# hf-controller.net
KiCad netlist of a schematic drawn in EAGLE
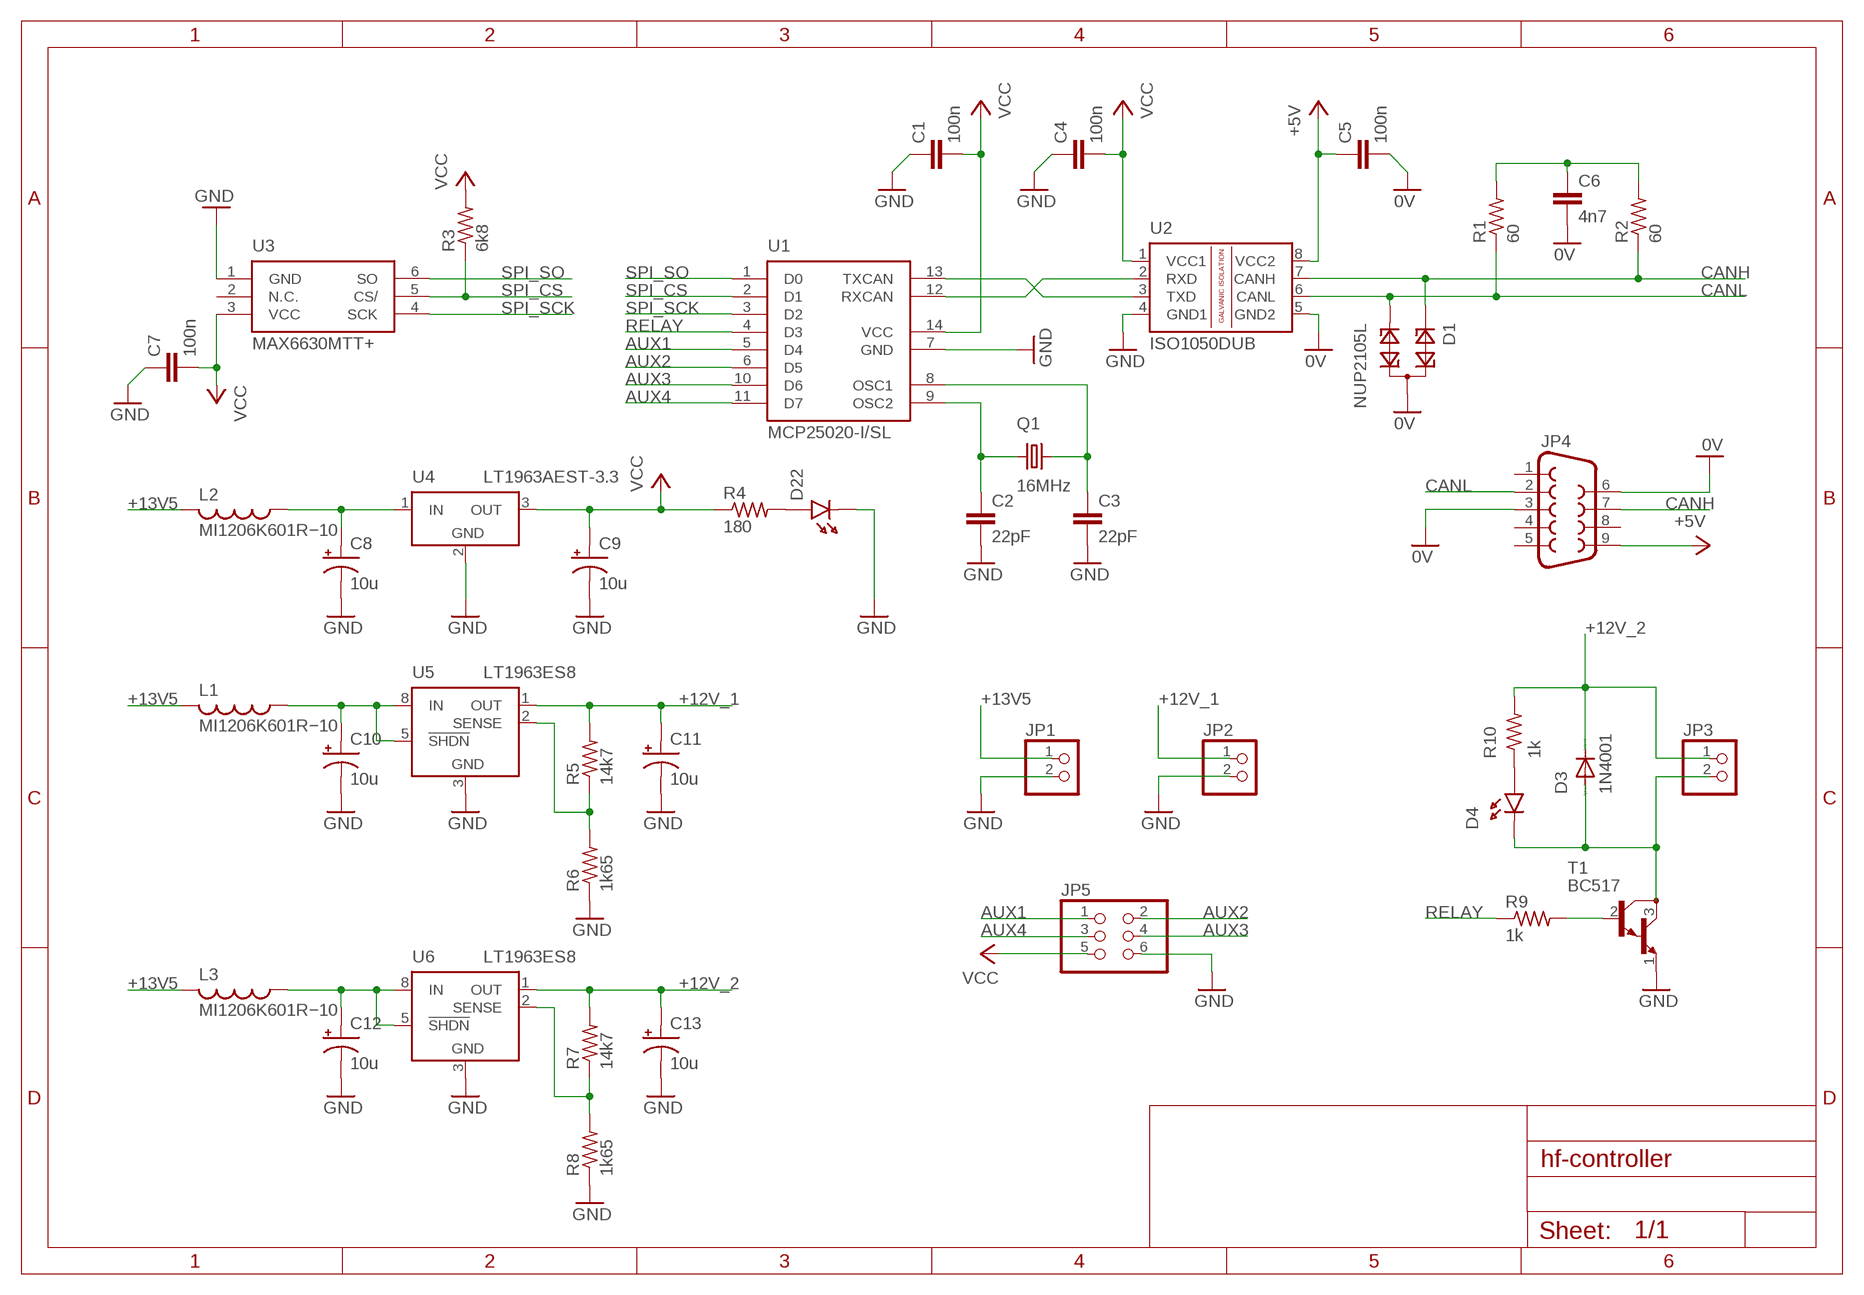
[diagram p0: schematic, sheet 1]

(export (version "E")
  (design (tool "Eeschema 10.0.6"))
  (components
    (comp (ref "C1")
      (value "100n")
      (footprint "eagle-import:C0805")
      (libsource (lib "eagle-import") (part "C-EUC0805"))
    )
    (comp (ref "C2")
      (value "22pF")
      (footprint "eagle-import:C0805")
      (libsource (lib "eagle-import") (part "C-EUC0805"))
    )
    (comp (ref "C3")
      (value "22pF")
      (footprint "eagle-import:C0805")
      (libsource (lib "eagle-import") (part "C-EUC0805"))
    )
    (comp (ref "C4")
      (value "100n")
      (footprint "eagle-import:C0805")
      (libsource (lib "eagle-import") (part "C-EUC0805"))
    )
    (comp (ref "C5")
      (value "100n")
      (footprint "eagle-import:C0805")
      (libsource (lib "eagle-import") (part "C-EUC0805"))
    )
    (comp (ref "C6")
      (value "4n7")
      (footprint "eagle-import:C0805")
      (libsource (lib "eagle-import") (part "C-EUC0805"))
    )
    (comp (ref "C7")
      (value "100n")
      (footprint "eagle-import:C0805")
      (libsource (lib "eagle-import") (part "C-EUC0805"))
    )
    (comp (ref "C8")
      (value "10u")
      (footprint "eagle-import:CAPACITOR_POL_1210")
      (libsource (lib "eagle-import") (part "CAPACITOR_POL1012"))
    )
    (comp (ref "C9")
      (value "10u")
      (footprint "eagle-import:CAPACITOR_POL_1210")
      (libsource (lib "eagle-import") (part "CAPACITOR_POL1012"))
    )
    (comp (ref "C10")
      (value "10u")
      (footprint "eagle-import:CAPACITOR_POL_1210")
      (libsource (lib "eagle-import") (part "CAPACITOR_POL1012"))
    )
    (comp (ref "C11")
      (value "10u")
      (footprint "eagle-import:CAPACITOR_POL_1210")
      (libsource (lib "eagle-import") (part "CAPACITOR_POL1012"))
    )
    (comp (ref "C12")
      (value "10u")
      (footprint "eagle-import:CAPACITOR_POL_1210")
      (libsource (lib "eagle-import") (part "CAPACITOR_POL1012"))
    )
    (comp (ref "C13")
      (value "10u")
      (footprint "eagle-import:CAPACITOR_POL_1210")
      (libsource (lib "eagle-import") (part "CAPACITOR_POL1012"))
    )
    (comp (ref "D1")
      (value "NUP2105L")
      (footprint "eagle-import:SOT23")
      (libsource (lib "eagle-import") (part "PESD1CAN"))
    )
    (comp (ref "D3")
      (value "1N4001")
      (footprint "eagle-import:DO41-10")
      (libsource (lib "eagle-import") (part "DIODE-DO41-10"))
    )
    (comp (ref "D4")
      (value "LED")
      (footprint "eagle-import:LED_1206")
      (libsource (lib "eagle-import") (part "LED"))
    )
    (comp (ref "D22")
      (value "LED")
      (footprint "eagle-import:LED_1206")
      (libsource (lib "eagle-import") (part "LED"))
    )
    (comp (ref "JP1")
      (value "PINHD-1X2")
      (footprint "eagle-import:1X02")
      (libsource (lib "eagle-import") (part "PINHD-1X2"))
    )
    (comp (ref "JP2")
      (value "PINHD-1X2")
      (footprint "eagle-import:1X02")
      (libsource (lib "eagle-import") (part "PINHD-1X2"))
    )
    (comp (ref "JP3")
      (value "PINHD-1X2")
      (footprint "eagle-import:1X02")
      (libsource (lib "eagle-import") (part "PINHD-1X2"))
    )
    (comp (ref "JP4")
      (value "F09HP")
      (footprint "eagle-import:F09HP")
      (libsource (lib "eagle-import") (part "F09HP"))
    )
    (comp (ref "JP5")
      (value "PINHD-2X3")
      (footprint "eagle-import:2X03")
      (libsource (lib "eagle-import") (part "PINHD-2X3"))
    )
    (comp (ref "L1")
      (value "MI1206K601R−10")
      (footprint "eagle-import:L3216C")
      (libsource (lib "eagle-import") (part "L-USL3216C"))
    )
    (comp (ref "L2")
      (value "MI1206K601R−10")
      (footprint "eagle-import:L3216C")
      (libsource (lib "eagle-import") (part "L-USL3216C"))
    )
    (comp (ref "L3")
      (value "MI1206K601R−10")
      (footprint "eagle-import:L3216C")
      (libsource (lib "eagle-import") (part "L-USL3216C"))
    )
    (comp (ref "Q1")
      (value "16MHz")
      (footprint "eagle-import:HC49_S")
      (libsource (lib "eagle-import") (part "CRYSTALHC49S"))
    )
    (comp (ref "R1")
      (value "60")
      (footprint "eagle-import:M0805")
      (libsource (lib "eagle-import") (part "resistor_R-US_M0805"))
    )
    (comp (ref "R2")
      (value "60")
      (footprint "eagle-import:M0805")
      (libsource (lib "eagle-import") (part "resistor_R-US_M0805"))
    )
    (comp (ref "R3")
      (value "6k8")
      (footprint "eagle-import:R0805")
      (libsource (lib "eagle-import") (part "resistor_R-US_R0805"))
    )
    (comp (ref "R4")
      (value "180")
      (footprint "eagle-import:R0805")
      (libsource (lib "eagle-import") (part "R-US_R0805"))
    )
    (comp (ref "R5")
      (value "14k7")
      (footprint "eagle-import:R0805")
      (libsource (lib "eagle-import") (part "resistor_R-US_R0805"))
    )
    (comp (ref "R6")
      (value "1k65")
      (footprint "eagle-import:R0805")
      (libsource (lib "eagle-import") (part "resistor_R-US_R0805"))
    )
    (comp (ref "R7")
      (value "14k7")
      (footprint "eagle-import:R0805")
      (libsource (lib "eagle-import") (part "resistor_R-US_R0805"))
    )
    (comp (ref "R8")
      (value "1k65")
      (footprint "eagle-import:R0805")
      (libsource (lib "eagle-import") (part "resistor_R-US_R0805"))
    )
    (comp (ref "R9")
      (value "1k")
      (footprint "eagle-import:R0805")
      (libsource (lib "eagle-import") (part "R-US_R0805"))
    )
    (comp (ref "R10")
      (value "1k")
      (footprint "eagle-import:R1206")
      (libsource (lib "eagle-import") (part "resistor_R-US_R1206"))
    )
    (comp (ref "T1")
      (value "BC517")
      (footprint "eagle-import:TO92")
      (libsource (lib "eagle-import") (part "BC517"))
    )
    (comp (ref "U1")
      (value "MCP25020-I/SL")
      (footprint "eagle-import:MCP25050")
      (libsource (lib "eagle-import") (part "MCP25050"))
    )
    (comp (ref "U2")
      (value "ISO1050DUB")
      (footprint "eagle-import:DUB-R-PDSO-G8")
      (fields (field (name "MPN") "ISO1050DUBR"))
      (libsource (lib "eagle-import") (part "ISO1050DUB"))
    )
    (comp (ref "U3")
      (value "MAX6630MTT+")
      (footprint "eagle-import:MAX6630MTT+")
      (libsource (lib "eagle-import") (part "MAX6630MTT+"))
    )
    (comp (ref "U4")
      (value "LT1963AEST-3.3")
      (footprint "eagle-import:SOT223")
      (fields (field (name "MPN") "LT1963EST-3.3"))
      (libsource (lib "eagle-import") (part "LT1963EST-3.3"))
    )
    (comp (ref "U5")
      (value "LT1963ES8")
      (footprint "eagle-import:SOIC8")
      (libsource (lib "eagle-import") (part "LT1963ES8"))
    )
    (comp (ref "U6")
      (value "LT1963ES8")
      (footprint "eagle-import:SOIC8")
      (libsource (lib "eagle-import") (part "LT1963ES8"))
    )
  )
  (nets
    (net (code "1") (name "+5V") (class "Default")
      (node (ref "C5") (pin "1") (pinfunction "1_1") (pintype "passive"))
      (node (ref "JP4") (pin "9") (pinfunction "9_9") (pintype "passive"))
      (node (ref "U2") (pin "8") (pinfunction "VCC2_8") (pintype "input"))
    )
    (net (code "2") (name "/+12V_1") (class "Default")
      (node (ref "C11") (pin "A") (pinfunction "A_A") (pintype "passive"))
      (node (ref "JP2") (pin "1") (pinfunction "1_1") (pintype "passive"))
      (node (ref "R5") (pin "2") (pinfunction "2_2") (pintype "passive"))
      (node (ref "U5") (pin "1") (pinfunction "OUT_1") (pintype "output"))
    )
    (net (code "3") (name "/+12V_2") (class "Default")
      (node (ref "C13") (pin "A") (pinfunction "A_A") (pintype "passive"))
      (node (ref "D3") (pin "C") (pinfunction "C_C") (pintype "passive"))
      (node (ref "JP3") (pin "1") (pinfunction "1_1") (pintype "passive"))
      (node (ref "R10") (pin "2") (pinfunction "2_2") (pintype "passive"))
      (node (ref "R7") (pin "2") (pinfunction "2_2") (pintype "passive"))
      (node (ref "U6") (pin "1") (pinfunction "OUT_1") (pintype "output"))
    )
    (net (code "4") (name "/+13V5") (class "Default")
      (node (ref "JP1") (pin "1") (pinfunction "1_1") (pintype "passive"))
      (node (ref "L1") (pin "2") (pinfunction "2_2") (pintype "passive"))
      (node (ref "L2") (pin "2") (pinfunction "2_2") (pintype "passive"))
      (node (ref "L3") (pin "2") (pinfunction "2_2") (pintype "passive"))
    )
    (net (code "5") (name "/AUX1") (class "Default")
      (node (ref "JP5") (pin "1") (pinfunction "1_1") (pintype "passive"))
      (node (ref "U1") (pin "5") (pinfunction "D4_5") (pintype "bidirectional"))
    )
    (net (code "6") (name "/AUX2") (class "Default")
      (node (ref "JP5") (pin "2") (pinfunction "2_2") (pintype "passive"))
      (node (ref "U1") (pin "6") (pinfunction "D5_6") (pintype "bidirectional"))
    )
    (net (code "7") (name "/AUX3") (class "Default")
      (node (ref "JP5") (pin "4") (pinfunction "4_4") (pintype "passive"))
      (node (ref "U1") (pin "10") (pinfunction "D6_10") (pintype "bidirectional"))
    )
    (net (code "8") (name "/AUX4") (class "Default")
      (node (ref "JP5") (pin "3") (pinfunction "3_3") (pintype "passive"))
      (node (ref "U1") (pin "11") (pinfunction "D7_11") (pintype "bidirectional"))
    )
    (net (code "9") (name "/CANH") (class "Default")
      (node (ref "D1") (pin "1") (pinfunction "1_1") (pintype "passive"))
      (node (ref "JP4") (pin "7") (pinfunction "7_7") (pintype "passive"))
      (node (ref "R2") (pin "1") (pinfunction "1_1") (pintype "passive"))
      (node (ref "U2") (pin "7") (pinfunction "CANH_7") (pintype "input"))
    )
    (net (code "10") (name "/CANL") (class "Default")
      (node (ref "D1") (pin "2") (pinfunction "2_2") (pintype "passive"))
      (node (ref "JP4") (pin "2") (pinfunction "2_2") (pintype "passive"))
      (node (ref "R1") (pin "1") (pinfunction "1_1") (pintype "passive"))
      (node (ref "U2") (pin "6") (pinfunction "CANL_6") (pintype "input"))
    )
    (net (code "11") (name "/RELAY") (class "Default")
      (node (ref "R9") (pin "1") (pinfunction "1_1") (pintype "passive"))
      (node (ref "U1") (pin "4") (pinfunction "D3_4") (pintype "bidirectional"))
    )
    (net (code "12") (name "/SPI_CS") (class "Default")
      (node (ref "R3") (pin "1") (pinfunction "1_1") (pintype "passive"))
      (node (ref "U1") (pin "2") (pinfunction "D1_2") (pintype "bidirectional"))
      (node (ref "U3") (pin "5") (pinfunction "CS/_5") (pintype "bidirectional"))
    )
    (net (code "13") (name "/SPI_SCK") (class "Default")
      (node (ref "U1") (pin "3") (pinfunction "D2_3") (pintype "bidirectional"))
      (node (ref "U3") (pin "4") (pinfunction "SCK_4") (pintype "bidirectional"))
    )
    (net (code "14") (name "/SPI_SO") (class "Default")
      (node (ref "U1") (pin "1") (pinfunction "D0_1") (pintype "bidirectional"))
      (node (ref "U3") (pin "6") (pinfunction "SO_6") (pintype "bidirectional"))
    )
    (net (code "15") (name "0V") (class "Default")
      (node (ref "C5") (pin "2") (pinfunction "2_2") (pintype "passive"))
      (node (ref "C6") (pin "2") (pinfunction "2_2") (pintype "passive"))
      (node (ref "D1") (pin "3") (pinfunction "3_3") (pintype "passive"))
      (node (ref "JP4") (pin "3") (pinfunction "3_3") (pintype "passive"))
      (node (ref "JP4") (pin "6") (pinfunction "6_6") (pintype "passive"))
      (node (ref "U2") (pin "5") (pinfunction "GND2_5") (pintype "input"))
    )
    (net (code "16") (name "GND") (class "Default")
      (node (ref "C1") (pin "1") (pinfunction "1_1") (pintype "passive"))
      (node (ref "C10") (pin "C") (pinfunction "C_C") (pintype "passive"))
      (node (ref "C11") (pin "C") (pinfunction "C_C") (pintype "passive"))
      (node (ref "C12") (pin "C") (pinfunction "C_C") (pintype "passive"))
      (node (ref "C13") (pin "C") (pinfunction "C_C") (pintype "passive"))
      (node (ref "C2") (pin "2") (pinfunction "2_2") (pintype "passive"))
      (node (ref "C3") (pin "2") (pinfunction "2_2") (pintype "passive"))
      (node (ref "C4") (pin "1") (pinfunction "1_1") (pintype "passive"))
      (node (ref "C7") (pin "1") (pinfunction "1_1") (pintype "passive"))
      (node (ref "C8") (pin "C") (pinfunction "C_C") (pintype "passive"))
      (node (ref "C9") (pin "C") (pinfunction "C_C") (pintype "passive"))
      (node (ref "D22") (pin "C") (pinfunction "C_C") (pintype "passive"))
      (node (ref "JP1") (pin "2") (pinfunction "2_2") (pintype "passive"))
      (node (ref "JP2") (pin "2") (pinfunction "2_2") (pintype "passive"))
      (node (ref "JP5") (pin "6") (pinfunction "6_6") (pintype "passive"))
      (node (ref "R6") (pin "1") (pinfunction "1_1") (pintype "passive"))
      (node (ref "R8") (pin "1") (pinfunction "1_1") (pintype "passive"))
      (node (ref "T1") (pin "1") (pinfunction "E_1") (pintype "passive"))
      (node (ref "U1") (pin "7") (pinfunction "GND_7") (pintype "power_in"))
      (node (ref "U2") (pin "4") (pinfunction "GND1_4") (pintype "input"))
      (node (ref "U3") (pin "1") (pinfunction "GND_1") (pintype "power_in"))
      (node (ref "U4") (pin "2") (pinfunction "GND_2") (pintype "power_in"))
      (node (ref "U5") (pin "3") (pinfunction "GND_3") (pintype "power_in"))
      (node (ref "U6") (pin "3") (pinfunction "GND_3") (pintype "power_in"))
    )
    (net (code "17") (name "Net-(C6-Pad1)") (class "Default")
      (node (ref "C6") (pin "1") (pinfunction "1_1") (pintype "passive"))
      (node (ref "R1") (pin "2") (pinfunction "2_2") (pintype "passive"))
      (node (ref "R2") (pin "2") (pinfunction "2_2") (pintype "passive"))
    )
    (net (code "18") (name "Net-(D4-PadA)") (class "Default")
      (node (ref "D4") (pin "A") (pinfunction "A_A") (pintype "passive"))
      (node (ref "R10") (pin "1") (pinfunction "1_1") (pintype "passive"))
    )
    (net (code "19") (name "Net-(D22-PadA)") (class "Default")
      (node (ref "D22") (pin "A") (pinfunction "A_A") (pintype "passive"))
      (node (ref "R4") (pin "2") (pinfunction "2_2") (pintype "passive"))
    )
    (net (code "20") (name "Net-(T1-B)") (class "Default")
      (node (ref "R9") (pin "2") (pinfunction "2_2") (pintype "passive"))
      (node (ref "T1") (pin "2") (pinfunction "B_2") (pintype "passive"))
    )
    (net (code "21") (name "Net-(T1-C)") (class "Default")
      (node (ref "D3") (pin "A") (pinfunction "A_A") (pintype "passive"))
      (node (ref "D4") (pin "C") (pinfunction "C_C") (pintype "passive"))
      (node (ref "JP3") (pin "2") (pinfunction "2_2") (pintype "passive"))
      (node (ref "T1") (pin "3") (pinfunction "C_3") (pintype "passive"))
    )
    (net (code "22") (name "Net-(U1-OSC1)") (class "Default")
      (node (ref "C3") (pin "1") (pinfunction "1_1") (pintype "passive"))
      (node (ref "Q1") (pin "2") (pinfunction "2_2") (pintype "passive"))
      (node (ref "U1") (pin "8") (pinfunction "OSC1_8") (pintype "bidirectional"))
    )
    (net (code "23") (name "Net-(U1-OSC2)") (class "Default")
      (node (ref "C2") (pin "1") (pinfunction "1_1") (pintype "passive"))
      (node (ref "Q1") (pin "1") (pinfunction "1_1") (pintype "passive"))
      (node (ref "U1") (pin "9") (pinfunction "OSC2_9") (pintype "bidirectional"))
    )
    (net (code "24") (name "Net-(U1-RXCAN)") (class "Default")
      (node (ref "U1") (pin "12") (pinfunction "RXCAN_12") (pintype "bidirectional"))
      (node (ref "U2") (pin "2") (pinfunction "RXD_2") (pintype "input"))
    )
    (net (code "25") (name "Net-(U1-TXCAN)") (class "Default")
      (node (ref "U1") (pin "13") (pinfunction "TXCAN_13") (pintype "bidirectional"))
      (node (ref "U2") (pin "3") (pinfunction "TXD_3") (pintype "input"))
    )
    (net (code "26") (name "Net-(U4A-IN)") (class "Default")
      (node (ref "C8") (pin "A") (pinfunction "A_A") (pintype "passive"))
      (node (ref "L2") (pin "1") (pinfunction "1_1") (pintype "passive"))
      (node (ref "U4") (pin "1") (pinfunction "IN_1") (pintype "input"))
    )
    (net (code "27") (name "Net-(U5A-IN)") (class "Default")
      (node (ref "C10") (pin "A") (pinfunction "A_A") (pintype "passive"))
      (node (ref "L1") (pin "1") (pinfunction "1_1") (pintype "passive"))
      (node (ref "U5") (pin "5") (pinfunction "~{SHDN}_5") (pintype "input"))
      (node (ref "U5") (pin "8") (pinfunction "IN_8") (pintype "input"))
    )
    (net (code "28") (name "Net-(U5A-SENSE)") (class "Default")
      (node (ref "R5") (pin "1") (pinfunction "1_1") (pintype "passive"))
      (node (ref "R6") (pin "2") (pinfunction "2_2") (pintype "passive"))
      (node (ref "U5") (pin "2") (pinfunction "SENSE_2") (pintype "input"))
    )
    (net (code "29") (name "Net-(U6A-IN)") (class "Default")
      (node (ref "C12") (pin "A") (pinfunction "A_A") (pintype "passive"))
      (node (ref "L3") (pin "1") (pinfunction "1_1") (pintype "passive"))
      (node (ref "U6") (pin "5") (pinfunction "~{SHDN}_5") (pintype "input"))
      (node (ref "U6") (pin "8") (pinfunction "IN_8") (pintype "input"))
    )
    (net (code "30") (name "Net-(U6A-SENSE)") (class "Default")
      (node (ref "R7") (pin "1") (pinfunction "1_1") (pintype "passive"))
      (node (ref "R8") (pin "2") (pinfunction "2_2") (pintype "passive"))
      (node (ref "U6") (pin "2") (pinfunction "SENSE_2") (pintype "input"))
    )
    (net (code "31") (name "VCC") (class "Default")
      (node (ref "C1") (pin "2") (pinfunction "2_2") (pintype "passive"))
      (node (ref "C4") (pin "2") (pinfunction "2_2") (pintype "passive"))
      (node (ref "C7") (pin "2") (pinfunction "2_2") (pintype "passive"))
      (node (ref "C9") (pin "A") (pinfunction "A_A") (pintype "passive"))
      (node (ref "JP5") (pin "5") (pinfunction "5_5") (pintype "passive"))
      (node (ref "R3") (pin "2") (pinfunction "2_2") (pintype "passive"))
      (node (ref "R4") (pin "1") (pinfunction "1_1") (pintype "passive"))
      (node (ref "U1") (pin "14") (pinfunction "VCC_14") (pintype "power_in"))
      (node (ref "U2") (pin "1") (pinfunction "VCC1_1") (pintype "input"))
      (node (ref "U3") (pin "3") (pinfunction "VCC_3") (pintype "power_in"))
      (node (ref "U4") (pin "3") (pinfunction "OUT_3") (pintype "passive"))
    )
    (net (code "32") (name "unconnected-(JP4-Pad1)") (class "Default")
      (node (ref "JP4") (pin "1") (pinfunction "1_1") (pintype "passive"))
    )
    (net (code "33") (name "unconnected-(JP4-Pad4)") (class "Default")
      (node (ref "JP4") (pin "4") (pinfunction "4_4") (pintype "passive"))
    )
    (net (code "34") (name "unconnected-(JP4-Pad5)") (class "Default")
      (node (ref "JP4") (pin "5") (pinfunction "5_5") (pintype "passive"))
    )
    (net (code "35") (name "unconnected-(JP4-Pad8)") (class "Default")
      (node (ref "JP4") (pin "8") (pinfunction "8_8") (pintype "passive"))
    )
    (net (code "36") (name "unconnected-(U3-N.C.-Pad2)") (class "Default")
      (node (ref "U3") (pin "2") (pinfunction "N.C._2") (pintype "no_connect"))
    )
  )
)
